# led_dimmer2.net
KiCad netlist of a schematic drawn in EAGLE
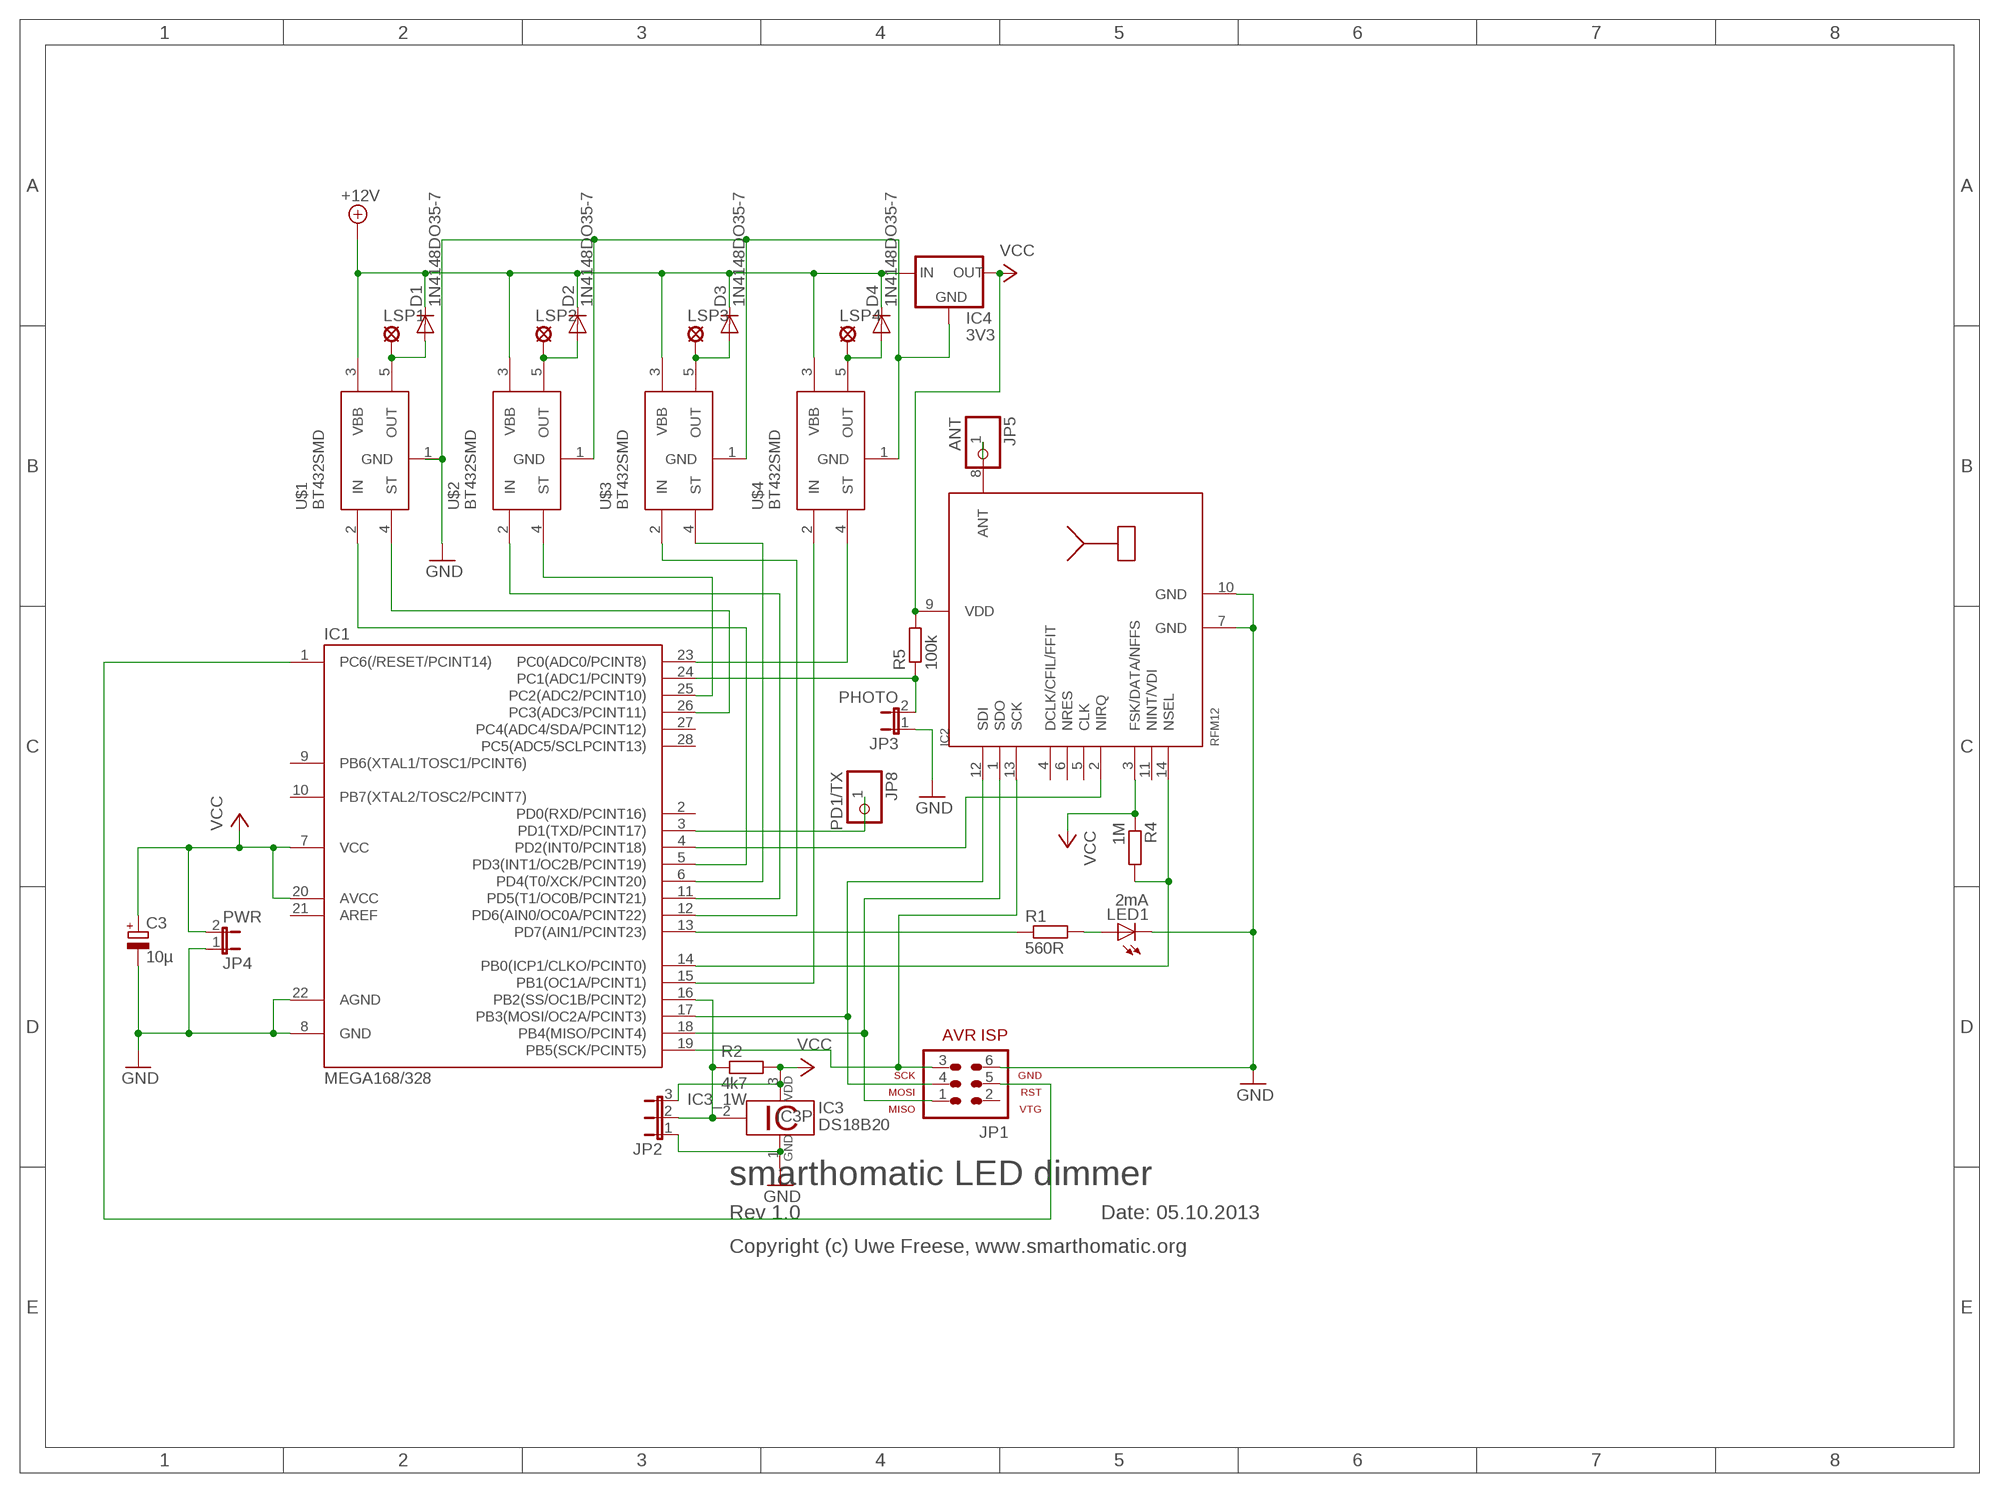
[diagram p0: schematic, sheet 1]

(export (version "E")
  (design (tool "Eeschema 10.0.6"))
  (components
    (comp (ref "C3")
      (value "10µ")
      (footprint "eagle-import:E2,5-6")
      (libsource (lib "eagle-import") (part "CPOL-EUE2.5-6"))
    )
    (comp (ref "D1")
      (value "1N4148DO35-7")
      (footprint "eagle-import:DO35-7")
      (libsource (lib "eagle-import") (part "1N4148DO35-7"))
    )
    (comp (ref "D2")
      (value "1N4148DO35-7")
      (footprint "eagle-import:DO35-7")
      (libsource (lib "eagle-import") (part "1N4148DO35-7"))
    )
    (comp (ref "D3")
      (value "1N4148DO35-7")
      (footprint "eagle-import:DO35-7")
      (libsource (lib "eagle-import") (part "1N4148DO35-7"))
    )
    (comp (ref "D4")
      (value "1N4148DO35-7")
      (footprint "eagle-import:DO35-7")
      (libsource (lib "eagle-import") (part "1N4148DO35-7"))
    )
    (comp (ref "IC1")
      (value "MEGA168/328")
      (footprint "eagle-import:DIL28-3")
      (libsource (lib "eagle-import") (part "MEGA48/88/168-PU"))
    )
    (comp (ref "IC2")
      (value "RFM12")
      (footprint "eagle-import:RFM")
      (libsource (lib "eagle-import") (part "RFM12"))
    )
    (comp (ref "IC3")
      (value "DS18B20")
      (footprint "eagle-import:TO92-")
      (libsource (lib "eagle-import") (part "DS18B20"))
    )
    (comp (ref "IC4")
      (value "3V3")
      (footprint "eagle-import:78LXX")
      (libsource (lib "eagle-import") (part "78LXX"))
    )
    (comp (ref "JP1")
      (value "AVR-ISP-6")
      (footprint "eagle-import:AVR-ISP-6")
      (libsource (lib "eagle-import") (part "AVR-ISP-6"))
    )
    (comp (ref "JP2")
      (value "JP2E")
      (footprint "eagle-import:JP2")
      (libsource (lib "eagle-import") (part "JP2E"))
    )
    (comp (ref "JP3")
      (value "PHOTO")
      (footprint "eagle-import:JP1")
      (libsource (lib "eagle-import") (part "JP1E"))
    )
    (comp (ref "JP4")
      (value "PWR")
      (footprint "eagle-import:JP1")
      (libsource (lib "eagle-import") (part "JP1E"))
    )
    (comp (ref "JP5")
      (value "ANT")
      (footprint "eagle-import:1X01")
      (libsource (lib "eagle-import") (part "PINHD-1X1"))
    )
    (comp (ref "JP8")
      (value "PD1/TX")
      (footprint "eagle-import:1X01")
      (libsource (lib "eagle-import") (part "PINHD-1X1"))
    )
    (comp (ref "LED1")
      (value "2mA")
      (footprint "eagle-import:LED3MM")
      (libsource (lib "eagle-import") (part "LED3MM"))
    )
    (comp (ref "LSP1")
      (value "MCS10B")
      (footprint "eagle-import:MCS10B")
      (libsource (lib "eagle-import") (part "MCS10B"))
    )
    (comp (ref "LSP2")
      (value "MCS10B")
      (footprint "eagle-import:MCS10B")
      (libsource (lib "eagle-import") (part "MCS10B"))
    )
    (comp (ref "LSP3")
      (value "MCS10B")
      (footprint "eagle-import:MCS10B")
      (libsource (lib "eagle-import") (part "MCS10B"))
    )
    (comp (ref "LSP4")
      (value "MCS10B")
      (footprint "eagle-import:MCS10B")
      (libsource (lib "eagle-import") (part "MCS10B"))
    )
    (comp (ref "R1")
      (value "560R")
      (footprint "eagle-import:0207_7")
      (libsource (lib "eagle-import") (part "R-EU_0207/7"))
    )
    (comp (ref "R2")
      (value "4k7")
      (footprint "eagle-import:0207_7")
      (libsource (lib "eagle-import") (part "resistor_R-EU_0207/7"))
    )
    (comp (ref "R4")
      (value "1M")
      (footprint "eagle-import:0207_7")
      (libsource (lib "eagle-import") (part "R-EU_0207/7"))
    )
    (comp (ref "R5")
      (value "100k")
      (footprint "eagle-import:0207_7")
      (libsource (lib "eagle-import") (part "R-EU_0207/7"))
    )
    (comp (ref "U$1")
      (value "BT432SMD")
      (footprint "eagle-import:TO220-58")
      (libsource (lib "eagle-import") (part "BT432SMD"))
    )
    (comp (ref "U$2")
      (value "BT432SMD")
      (footprint "eagle-import:TO220-58")
      (libsource (lib "eagle-import") (part "BT432SMD"))
    )
    (comp (ref "U$3")
      (value "BT432SMD")
      (footprint "eagle-import:TO220-58")
      (libsource (lib "eagle-import") (part "BT432SMD"))
    )
    (comp (ref "U$4")
      (value "BT432SMD")
      (footprint "eagle-import:TO220-58")
      (libsource (lib "eagle-import") (part "BT432SMD"))
    )
  )
  (nets
    (net (code "1") (name "+12V") (class "Default")
      (node (ref "D1") (pin "C") (pinfunction "C_C") (pintype "passive"))
      (node (ref "D2") (pin "C") (pinfunction "C_C") (pintype "passive"))
      (node (ref "D3") (pin "C") (pinfunction "C_C") (pintype "passive"))
      (node (ref "D4") (pin "C") (pinfunction "C_C") (pintype "passive"))
      (node (ref "IC4") (pin "IN") (pinfunction "IN_IN") (pintype "input"))
      (node (ref "U$1") (pin "3") (pinfunction "VBB_3") (pintype "bidirectional"))
      (node (ref "U$2") (pin "3") (pinfunction "VBB_3") (pintype "bidirectional"))
      (node (ref "U$3") (pin "3") (pinfunction "VBB_3") (pintype "bidirectional"))
      (node (ref "U$4") (pin "3") (pinfunction "VBB_3") (pintype "bidirectional"))
    )
    (net (code "2") (name "GND") (class "Default")
      (node (ref "C3") (pin "-") (pinfunction "-_-") (pintype "passive"))
      (node (ref "IC1") (pin "22") (pinfunction "AGND_22") (pintype "power_in"))
      (node (ref "IC1") (pin "8") (pinfunction "GND_8") (pintype "power_in"))
      (node (ref "IC2") (pin "10") (pinfunction "GND_10") (pintype "power_in"))
      (node (ref "IC2") (pin "7") (pinfunction "GND_7") (pintype "power_in"))
      (node (ref "IC3") (pin "1") (pinfunction "GND_1") (pintype "power_in"))
      (node (ref "IC4") (pin "GND") (pinfunction "GND_GND") (pintype "input"))
      (node (ref "JP1") (pin "6") (pinfunction "6_6") (pintype "passive"))
      (node (ref "JP2") (pin "1") (pinfunction "1_1") (pintype "passive"))
      (node (ref "JP3") (pin "1") (pinfunction "1_1") (pintype "passive"))
      (node (ref "JP4") (pin "1") (pinfunction "1_1") (pintype "passive"))
      (node (ref "LED1") (pin "K") (pinfunction "C_K") (pintype "passive"))
      (node (ref "U$1") (pin "1") (pinfunction "GND_1") (pintype "bidirectional"))
      (node (ref "U$2") (pin "1") (pinfunction "GND_1") (pintype "bidirectional"))
      (node (ref "U$3") (pin "1") (pinfunction "GND_1") (pintype "bidirectional"))
      (node (ref "U$4") (pin "1") (pinfunction "GND_1") (pintype "bidirectional"))
    )
    (net (code "3") (name "Net-(IC1-PB0(ICP1{slash}CLKO{slash}PCINT0))") (class "Default")
      (node (ref "IC1") (pin "14") (pinfunction "PB0(ICP1/CLKO/PCINT0)_14") (pintype "bidirectional"))
      (node (ref "IC2") (pin "14") (pinfunction "NSEL_14") (pintype "bidirectional"))
      (node (ref "R4") (pin "2") (pinfunction "2_2") (pintype "passive"))
    )
    (net (code "4") (name "Net-(IC1-PB1(OC1A{slash}PCINT1))") (class "Default")
      (node (ref "IC1") (pin "15") (pinfunction "PB1(OC1A/PCINT1)_15") (pintype "bidirectional"))
      (node (ref "U$4") (pin "2") (pinfunction "IN_2") (pintype "bidirectional"))
    )
    (net (code "5") (name "Net-(IC1-PB2(SS{slash}OC1B{slash}PCINT2))") (class "Default")
      (node (ref "IC1") (pin "16") (pinfunction "PB2(SS/OC1B/PCINT2)_16") (pintype "bidirectional"))
      (node (ref "IC3") (pin "2") (pinfunction "1W_2") (pintype "power_in"))
      (node (ref "JP2") (pin "2") (pinfunction "2_2") (pintype "passive"))
      (node (ref "R2") (pin "1") (pinfunction "1_1") (pintype "passive"))
    )
    (net (code "6") (name "Net-(IC1-PB3(MOSI{slash}OC2A{slash}PCINT3))") (class "Default")
      (node (ref "IC1") (pin "17") (pinfunction "PB3(MOSI/OC2A/PCINT3)_17") (pintype "bidirectional"))
      (node (ref "IC2") (pin "12") (pinfunction "SDI_12") (pintype "bidirectional"))
      (node (ref "JP1") (pin "4") (pinfunction "4_4") (pintype "passive"))
    )
    (net (code "7") (name "Net-(IC1-PB4(MISO{slash}PCINT4))") (class "Default")
      (node (ref "IC1") (pin "18") (pinfunction "PB4(MISO/PCINT4)_18") (pintype "bidirectional"))
      (node (ref "IC2") (pin "1") (pinfunction "SDO_1") (pintype "bidirectional"))
      (node (ref "JP1") (pin "1") (pinfunction "1_1") (pintype "passive"))
    )
    (net (code "8") (name "Net-(IC1-PB5(SCK{slash}PCINT5))") (class "Default")
      (node (ref "IC1") (pin "19") (pinfunction "PB5(SCK/PCINT5)_19") (pintype "bidirectional"))
      (node (ref "IC2") (pin "13") (pinfunction "SCK_13") (pintype "bidirectional"))
      (node (ref "JP1") (pin "3") (pinfunction "3_3") (pintype "passive"))
    )
    (net (code "9") (name "Net-(IC1-PC0(ADC0{slash}PCINT8))") (class "Default")
      (node (ref "IC1") (pin "23") (pinfunction "PC0(ADC0/PCINT8)_23") (pintype "bidirectional"))
      (node (ref "U$4") (pin "4") (pinfunction "ST_4") (pintype "bidirectional"))
    )
    (net (code "10") (name "Net-(IC1-PC1(ADC1{slash}PCINT9))") (class "Default")
      (node (ref "IC1") (pin "24") (pinfunction "PC1(ADC1/PCINT9)_24") (pintype "bidirectional"))
      (node (ref "JP3") (pin "2") (pinfunction "2_2") (pintype "passive"))
      (node (ref "R5") (pin "1") (pinfunction "1_1") (pintype "passive"))
    )
    (net (code "11") (name "Net-(IC1-PC2(ADC2{slash}PCINT10))") (class "Default")
      (node (ref "IC1") (pin "25") (pinfunction "PC2(ADC2/PCINT10)_25") (pintype "bidirectional"))
      (node (ref "U$2") (pin "4") (pinfunction "ST_4") (pintype "bidirectional"))
    )
    (net (code "12") (name "Net-(IC1-PC3(ADC3{slash}PCINT11))") (class "Default")
      (node (ref "IC1") (pin "26") (pinfunction "PC3(ADC3/PCINT11)_26") (pintype "bidirectional"))
      (node (ref "U$1") (pin "4") (pinfunction "ST_4") (pintype "bidirectional"))
    )
    (net (code "13") (name "Net-(IC1-PC6({slash}RESET{slash}PCINT14))") (class "Default")
      (node (ref "IC1") (pin "1") (pinfunction "PC6(/RESET/PCINT14)_1") (pintype "bidirectional"))
      (node (ref "JP1") (pin "5") (pinfunction "5_5") (pintype "passive"))
    )
    (net (code "14") (name "Net-(IC1-PD1(TXD{slash}PCINT17))") (class "Default")
      (node (ref "IC1") (pin "3") (pinfunction "PD1(TXD/PCINT17)_3") (pintype "bidirectional"))
      (node (ref "JP8") (pin "1") (pinfunction "1_1") (pintype "passive"))
    )
    (net (code "15") (name "Net-(IC1-PD2(INT0{slash}PCINT18))") (class "Default")
      (node (ref "IC1") (pin "4") (pinfunction "PD2(INT0/PCINT18)_4") (pintype "bidirectional"))
      (node (ref "IC2") (pin "2") (pinfunction "NIRQ_2") (pintype "bidirectional"))
    )
    (net (code "16") (name "Net-(IC1-PD3(INT1{slash}OC2B{slash}PCINT19))") (class "Default")
      (node (ref "IC1") (pin "5") (pinfunction "PD3(INT1/OC2B/PCINT19)_5") (pintype "bidirectional"))
      (node (ref "U$1") (pin "2") (pinfunction "IN_2") (pintype "bidirectional"))
    )
    (net (code "17") (name "Net-(IC1-PD4(T0{slash}XCK{slash}PCINT20))") (class "Default")
      (node (ref "IC1") (pin "6") (pinfunction "PD4(T0/XCK/PCINT20)_6") (pintype "bidirectional"))
      (node (ref "U$3") (pin "4") (pinfunction "ST_4") (pintype "bidirectional"))
    )
    (net (code "18") (name "Net-(IC1-PD5(T1{slash}OC0B{slash}PCINT21))") (class "Default")
      (node (ref "IC1") (pin "11") (pinfunction "PD5(T1/OC0B/PCINT21)_11") (pintype "bidirectional"))
      (node (ref "U$2") (pin "2") (pinfunction "IN_2") (pintype "bidirectional"))
    )
    (net (code "19") (name "Net-(IC1-PD6(AIN0{slash}OC0A{slash}PCINT22))") (class "Default")
      (node (ref "IC1") (pin "12") (pinfunction "PD6(AIN0/OC0A/PCINT22)_12") (pintype "bidirectional"))
      (node (ref "U$3") (pin "2") (pinfunction "IN_2") (pintype "bidirectional"))
    )
    (net (code "20") (name "Net-(IC1-PD7(AIN1{slash}PCINT23))") (class "Default")
      (node (ref "IC1") (pin "13") (pinfunction "PD7(AIN1/PCINT23)_13") (pintype "bidirectional"))
      (node (ref "R1") (pin "1") (pinfunction "1_1") (pintype "passive"))
    )
    (net (code "21") (name "Net-(IC2-ANT)") (class "Default")
      (node (ref "IC2") (pin "8") (pinfunction "ANT_8") (pintype "output"))
      (node (ref "JP5") (pin "1") (pinfunction "1_1") (pintype "passive"))
    )
    (net (code "22") (name "Net-(LED1-PadA)") (class "Default")
      (node (ref "LED1") (pin "A") (pinfunction "A_A") (pintype "passive"))
      (node (ref "R1") (pin "2") (pinfunction "2_2") (pintype "passive"))
    )
    (net (code "23") (name "Net-(U$1-OUT)") (class "Default")
      (node (ref "D1") (pin "A") (pinfunction "A_A") (pintype "passive"))
      (node (ref "LSP1") (pin "MP") (pinfunction "MP_MP") (pintype "passive"))
      (node (ref "U$1") (pin "5") (pinfunction "OUT_5") (pintype "bidirectional"))
    )
    (net (code "24") (name "Net-(U$2-OUT)") (class "Default")
      (node (ref "D2") (pin "A") (pinfunction "A_A") (pintype "passive"))
      (node (ref "LSP2") (pin "MP") (pinfunction "MP_MP") (pintype "passive"))
      (node (ref "U$2") (pin "5") (pinfunction "OUT_5") (pintype "bidirectional"))
    )
    (net (code "25") (name "Net-(U$3-OUT)") (class "Default")
      (node (ref "D3") (pin "A") (pinfunction "A_A") (pintype "passive"))
      (node (ref "LSP3") (pin "MP") (pinfunction "MP_MP") (pintype "passive"))
      (node (ref "U$3") (pin "5") (pinfunction "OUT_5") (pintype "bidirectional"))
    )
    (net (code "26") (name "Net-(U$4-OUT)") (class "Default")
      (node (ref "D4") (pin "A") (pinfunction "A_A") (pintype "passive"))
      (node (ref "LSP4") (pin "MP") (pinfunction "MP_MP") (pintype "passive"))
      (node (ref "U$4") (pin "5") (pinfunction "OUT_5") (pintype "bidirectional"))
    )
    (net (code "27") (name "VCC") (class "Default")
      (node (ref "C3") (pin "+") (pinfunction "+_+") (pintype "passive"))
      (node (ref "IC1") (pin "20") (pinfunction "AVCC_20") (pintype "passive"))
      (node (ref "IC1") (pin "7") (pinfunction "VCC_7") (pintype "power_in"))
      (node (ref "IC2") (pin "3") (pinfunction "FSK/DATA/NFFS_3") (pintype "bidirectional"))
      (node (ref "IC2") (pin "9") (pinfunction "VDD_9") (pintype "power_in"))
      (node (ref "IC3") (pin "3") (pinfunction "VDD_3") (pintype "power_in"))
      (node (ref "IC4") (pin "OUT") (pinfunction "OUT_OUT") (pintype "passive"))
      (node (ref "JP2") (pin "3") (pinfunction "3_3") (pintype "passive"))
      (node (ref "JP4") (pin "2") (pinfunction "2_2") (pintype "passive"))
      (node (ref "R2") (pin "2") (pinfunction "2_2") (pintype "passive"))
      (node (ref "R4") (pin "1") (pinfunction "1_1") (pintype "passive"))
      (node (ref "R5") (pin "2") (pinfunction "2_2") (pintype "passive"))
    )
    (net (code "28") (name "unconnected-(IC1-AREF-Pad21)") (class "Default")
      (node (ref "IC1") (pin "21") (pinfunction "AREF_21") (pintype "passive"))
    )
    (net (code "29") (name "unconnected-(IC1-PB6(XTAL1{slash}TOSC1{slash}PCINT6)-Pad9)") (class "Default")
      (node (ref "IC1") (pin "9") (pinfunction "PB6(XTAL1/TOSC1/PCINT6)_9") (pintype "bidirectional"))
    )
    (net (code "30") (name "unconnected-(IC1-PB7(XTAL2{slash}TOSC2{slash}PCINT7)-Pad10)") (class "Default")
      (node (ref "IC1") (pin "10") (pinfunction "PB7(XTAL2/TOSC2/PCINT7)_10") (pintype "bidirectional"))
    )
    (net (code "31") (name "unconnected-(IC1-PC4(ADC4{slash}SDA{slash}PCINT12)-Pad27)") (class "Default")
      (node (ref "IC1") (pin "27") (pinfunction "PC4(ADC4/SDA/PCINT12)_27") (pintype "bidirectional"))
    )
    (net (code "32") (name "unconnected-(IC1-PC5(ADC5{slash}SCLPCINT13)-Pad28)") (class "Default")
      (node (ref "IC1") (pin "28") (pinfunction "PC5(ADC5/SCLPCINT13)_28") (pintype "bidirectional"))
    )
    (net (code "33") (name "unconnected-(IC1-PD0(RXD{slash}PCINT16)-Pad2)") (class "Default")
      (node (ref "IC1") (pin "2") (pinfunction "PD0(RXD/PCINT16)_2") (pintype "bidirectional"))
    )
    (net (code "34") (name "unconnected-(IC2-CLK-Pad5)") (class "Default")
      (node (ref "IC2") (pin "5") (pinfunction "CLK_5") (pintype "bidirectional"))
    )
    (net (code "35") (name "unconnected-(IC2-DCLK{slash}CFIL{slash}FFIT-Pad4)") (class "Default")
      (node (ref "IC2") (pin "4") (pinfunction "DCLK/CFIL/FFIT_4") (pintype "bidirectional"))
    )
    (net (code "36") (name "unconnected-(IC2-NINT{slash}VDI-Pad11)") (class "Default")
      (node (ref "IC2") (pin "11") (pinfunction "NINT/VDI_11") (pintype "bidirectional"))
    )
    (net (code "37") (name "unconnected-(IC2-NRES-Pad6)") (class "Default")
      (node (ref "IC2") (pin "6") (pinfunction "NRES_6") (pintype "bidirectional"))
    )
    (net (code "38") (name "unconnected-(JP1-Pad2)") (class "Default")
      (node (ref "JP1") (pin "2") (pinfunction "2_2") (pintype "passive"))
    )
  )
)
